# Sheet_1.net
KiCad netlist of a schematic drawn in Altium Designer
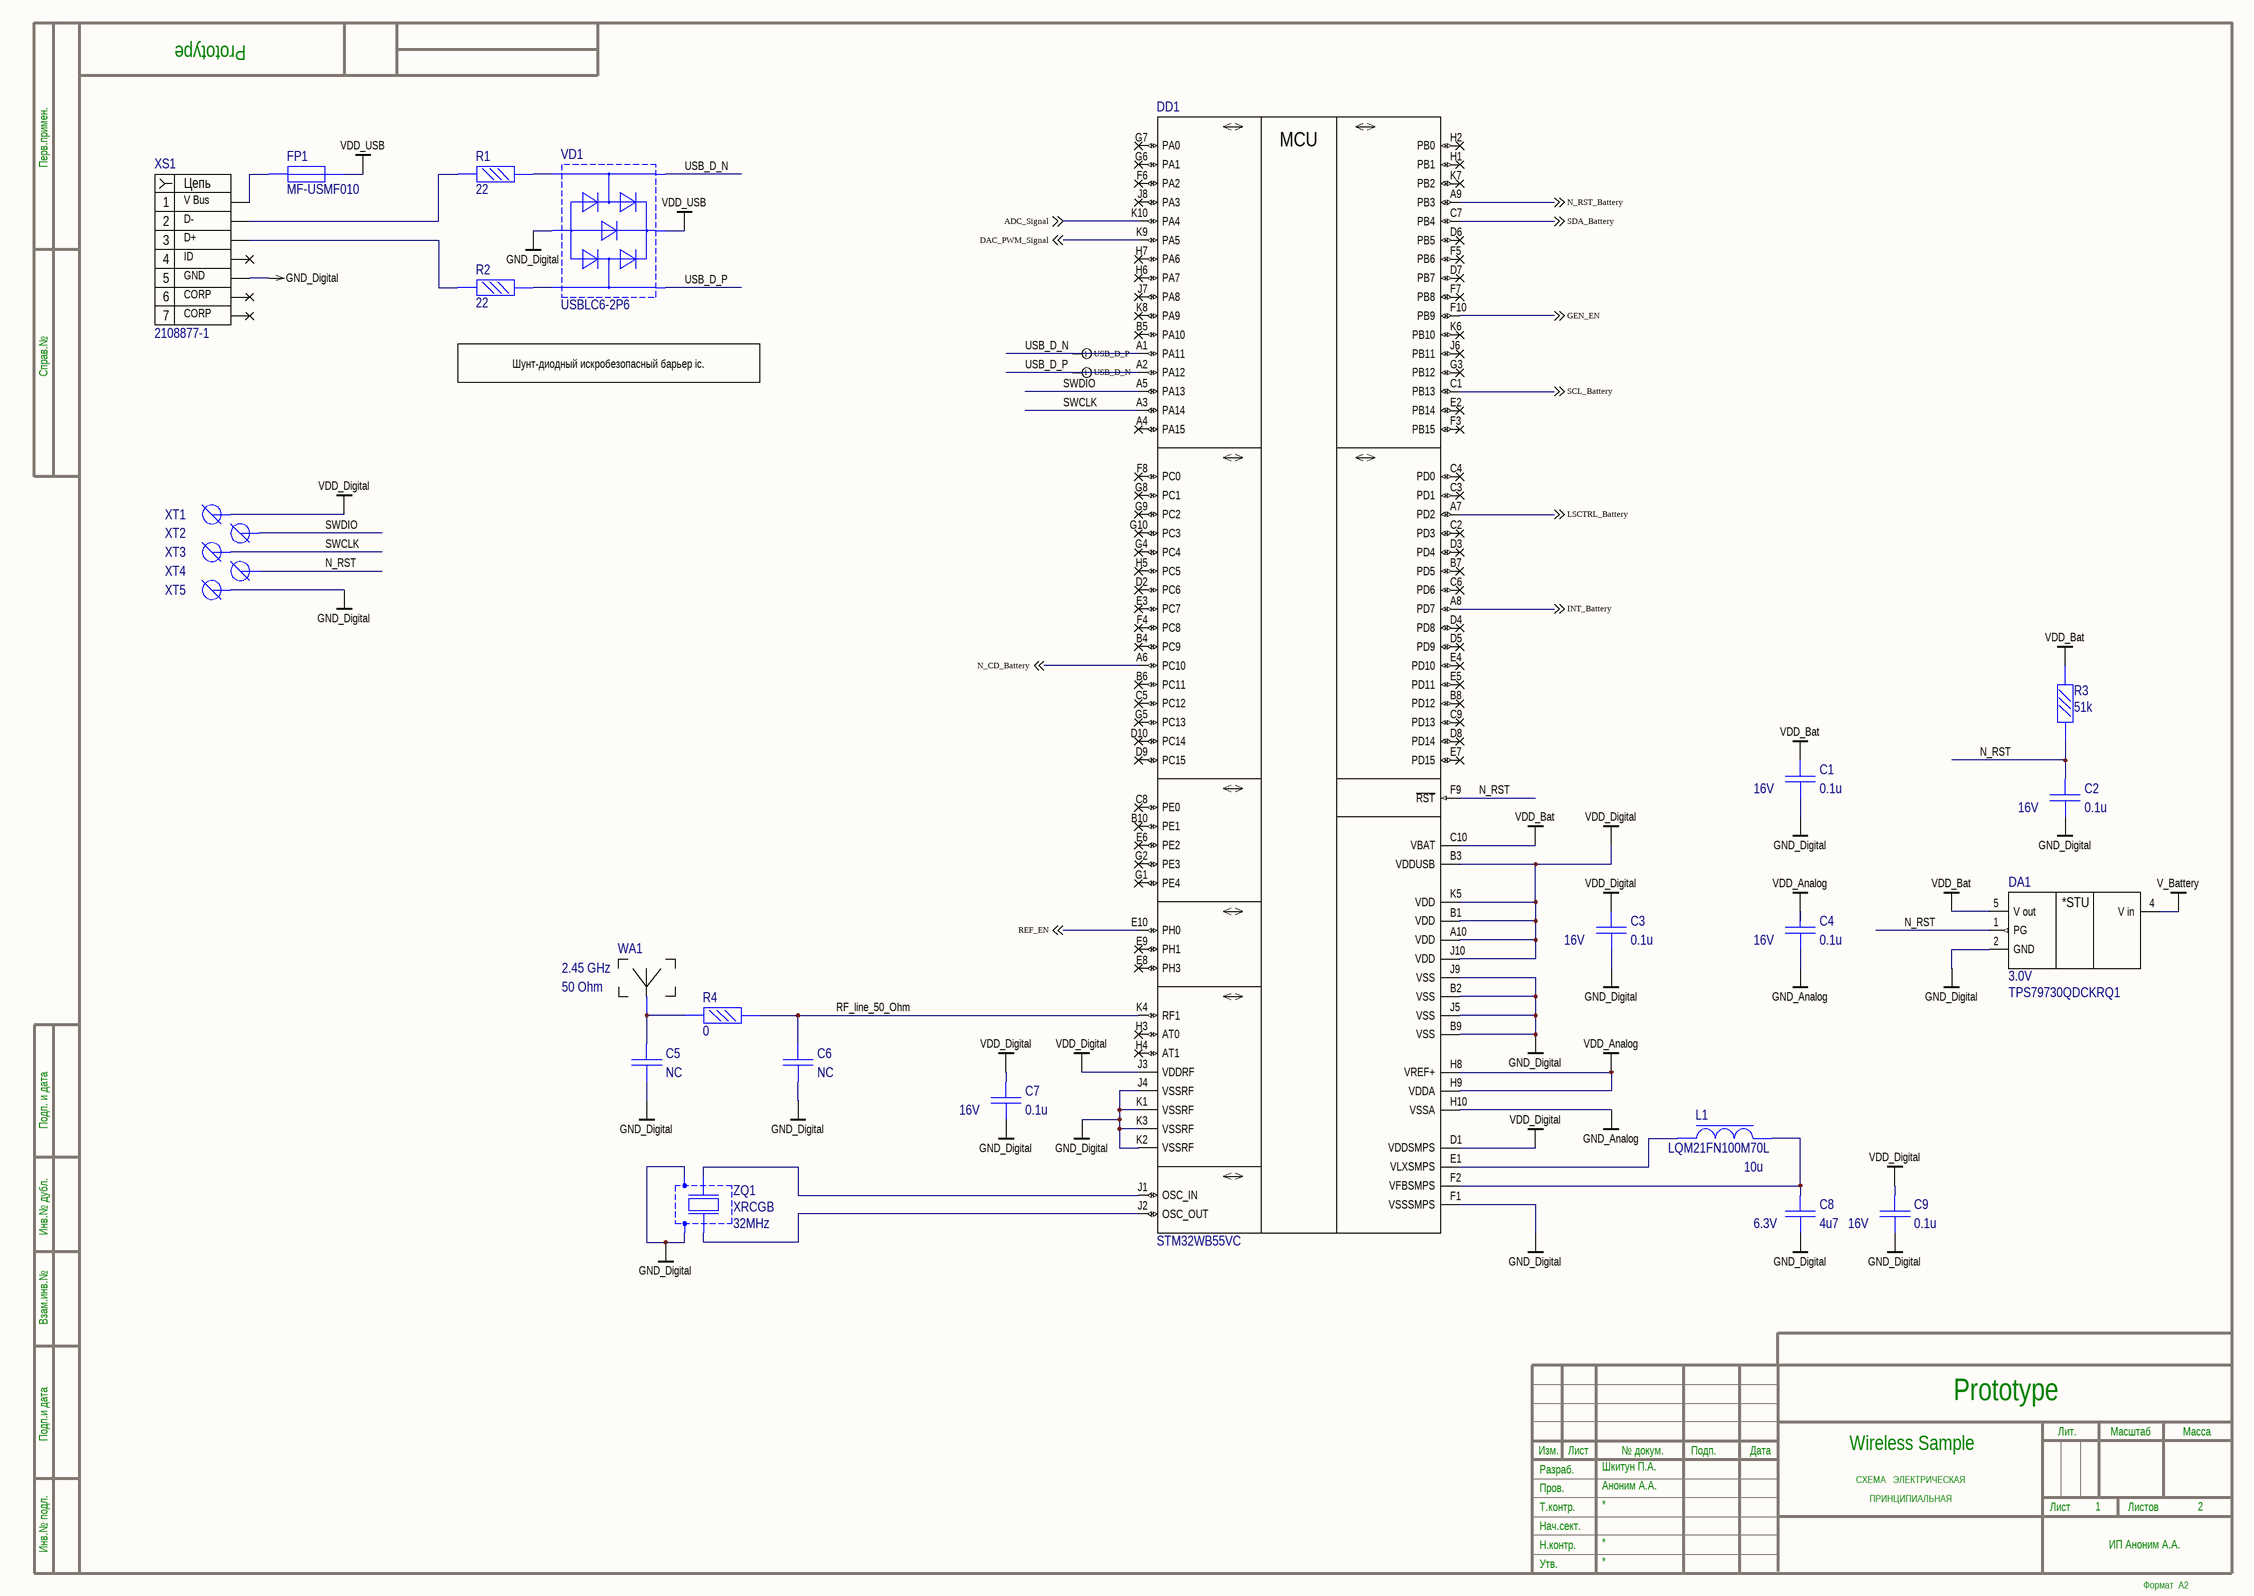
[diagram p0: Sheet_1.SchDoc]

(export (version "E")
  (design (tool "Eeschema 10.0.6"))
  (components
    (comp (ref "C1")
      (value "0.1u")
      (footprint "C0201_2")
      (fields
        (field (name "VOLTAGE") "16V")
        (field (name "Comment") "X7R")
        (field (name "PUBLISHER") "Andrew Danich")
      )
      (libsource (lib "Capacitor GOST") (part "X7R C0201"))
    )
    (comp (ref "C2")
      (value "0.1u")
      (footprint "C0201_2")
      (fields
        (field (name "VOLTAGE") "16V")
        (field (name "Comment") "X7R")
        (field (name "PUBLISHER") "Andrew Danich")
      )
      (libsource (lib "Capacitor GOST") (part "X7R C0201"))
    )
    (comp (ref "C3")
      (value "0.1u")
      (footprint "C0201_2")
      (fields
        (field (name "VOLTAGE") "16V")
        (field (name "Comment") "X7R")
        (field (name "PUBLISHER") "Andrew Danich")
      )
      (libsource (lib "Capacitor GOST") (part "X7R C0201"))
    )
    (comp (ref "C4")
      (value "0.1u")
      (footprint "C0201_2")
      (fields
        (field (name "VOLTAGE") "16V")
        (field (name "Comment") "X7R")
        (field (name "PUBLISHER") "Andrew Danich")
      )
      (libsource (lib "Capacitor GOST") (part "X7R C0201"))
    )
    (comp (ref "C5")
      (value "NC")
      (footprint "SMD Capacitor:C0201_C0G")
      (fields (field (name "Comment") "C0G") (field (name "PUBLISHER") "Andrew Danich"))
      (libsource (lib "Capacitor GOST") (part "C0G C0201"))
    )
    (comp (ref "C6")
      (value "NC")
      (footprint "SMD Capacitor:C0201_C0G")
      (fields (field (name "Comment") "C0G") (field (name "PUBLISHER") "Andrew Danich"))
      (libsource (lib "Capacitor GOST") (part "C0G C0201"))
    )
    (comp (ref "C7")
      (value "0.1u")
      (footprint "C0201_2")
      (fields
        (field (name "VOLTAGE") "16V")
        (field (name "Comment") "X7R")
        (field (name "PUBLISHER") "Andrew Danich")
      )
      (libsource (lib "Capacitor GOST") (part "X7R C0201"))
    )
    (comp (ref "C8")
      (value "4u7")
      (footprint "SMD Capacitor:C0603")
      (fields
        (field (name "VOLTAGE") "6.3V")
        (field (name "Comment") "X7R")
        (field (name "PUBLISHER") "Andrew Danich")
      )
      (libsource (lib "Capacitor GOST") (part "X7R C0603"))
    )
    (comp (ref "C9")
      (value "0.1u")
      (footprint "C0201_2")
      (fields
        (field (name "VOLTAGE") "16V")
        (field (name "Comment") "X7R")
        (field (name "PUBLISHER") "Andrew Danich")
      )
      (libsource (lib "Capacitor GOST") (part "X7R C0201"))
    )
    (comp (ref "DA1")
      (value "3.0V")
      (footprint "SMD SOT:SC70-5")
      (fields
        (field (name "NAME") "TPS79730QDCKRQ1")
        (field (name "Comment") "TPS79730QDCKRQ1")
        (field (name "PUBLISHER") "Andrew Danich")
      )
      (libsource (lib "Linear Regulator GOST") (part "TPS79730QDCKRQ1"))
    )
    (comp (ref "DD1")
      (value "STM32WB55VC")
      (footprint "SMD WLCSP:WLCSP-100")
      (fields (field (name "PUBLISHER") "Andrew Danich"))
      (libsource (lib "MCU GOST") (part "STM32WB55VC"))
    )
    (comp (ref "FP1")
      (value "MF-USMF010")
      (footprint "SMD Fuse:F1210")
      (fields (field (name "Comment") "MF-USM005") (field (name "PUBLISHER") "Andrew Danich"))
      (libsource (lib "Fuse GOST") (part "MF-USM005"))
    )
    (comp (ref "L1")
      (value "10u")
      (footprint "SMD Coil:L0805")
      (fields
        (field (name "NAME") "LQM21FN100M70L")
        (field (name "Comment") "LQM21FN100M70L")
        (field (name "PUBLISHER") "Andrew Danich")
      )
      (libsource (lib "Coil GOST") (part "LQM21FN100M70L"))
    )
    (comp (ref "R1")
      (value "22")
      (footprint "R0201_2")
      (fields (field (name "Comment") "ERJ1GN") (field (name "PUBLISHER") "Andrew Danich"))
      (libsource (lib "Resistor GOST") (part "R0201"))
    )
    (comp (ref "R2")
      (value "22")
      (footprint "R0201_2")
      (fields (field (name "Comment") "ERJ1GN") (field (name "PUBLISHER") "Andrew Danich"))
      (libsource (lib "Resistor GOST") (part "R0201"))
    )
    (comp (ref "R3")
      (value "51k")
      (footprint "R0201_2")
      (fields (field (name "Comment") "ERJ1GN") (field (name "PUBLISHER") "Andrew Danich"))
      (libsource (lib "Resistor GOST") (part "R0201"))
    )
    (comp (ref "R4")
      (value "0")
      (footprint "R0201_2")
      (fields (field (name "Comment") "ERJ1GN") (field (name "PUBLISHER") "Andrew Danich"))
      (libsource (lib "Resistor GOST") (part "R0201"))
    )
    (comp (ref "VD1")
      (value "USBLC6-2P6")
      (footprint "SMD SOT:SOT-666")
      (fields (field (name "PUBLISHER") "Andrew Danich"))
      (libsource (lib "Diode GOST") (part "USBLC6-2P6"))
    )
    (comp (ref "WA1")
      (value "2.45 GHz")
      (footprint "SMD Ant:AMCA31-2R450G-S1F-T3")
      (fields
        (field (name "Z") "50 Ohm")
        (field (name "Comment") "X7R")
        (field (name "PUBLISHER") "Andrew Danich")
      )
      (libsource (lib "Ant GOST") (part "AMCA31-2R450G-S1F-T3"))
    )
    (comp (ref "XS1")
      (value "2108877-1")
      (footprint "SMD Connector:2108877-1")
      (fields
        (field (name "7_LINE") "CORP")
        (field (name "6_LINE") "CORP")
        (field (name "1_LINE") "V Bus")
        (field (name "2_LINE") "D-")
        (field (name "3_LINE") "D+")
        (field (name "4_LINE") "ID")
        (field (name "5_LINE") "GND")
        (field (name "Comment") "2108877-1 TE Connectivity")
        (field (name "PUBLISHER") "Andrew Danich")
      )
      (libsource (lib "Connector GOST") (part "2108877-1"))
    )
    (comp (ref "XT1")
      (value "Test_Pin")
      (footprint "SMD Connector:TEST_PIN_2")
      (fields (field (name "PUBLISHER") "Andrew Danich"))
      (libsource (lib "Connector GOST") (part "Test_Pin"))
    )
    (comp (ref "XT2")
      (value "Test_Pin")
      (footprint "SMD Connector:TEST_PIN_2")
      (fields (field (name "PUBLISHER") "Andrew Danich"))
      (libsource (lib "Connector GOST") (part "Test_Pin"))
    )
    (comp (ref "XT3")
      (value "Test_Pin")
      (footprint "SMD Connector:TEST_PIN_2")
      (fields (field (name "PUBLISHER") "Andrew Danich"))
      (libsource (lib "Connector GOST") (part "Test_Pin"))
    )
    (comp (ref "XT4")
      (value "Test_Pin")
      (footprint "SMD Connector:TEST_PIN_2")
      (fields (field (name "PUBLISHER") "Andrew Danich"))
      (libsource (lib "Connector GOST") (part "Test_Pin"))
    )
    (comp (ref "XT5")
      (value "Test_Pin")
      (footprint "SMD Connector:TEST_PIN_2")
      (fields (field (name "PUBLISHER") "Andrew Danich"))
      (libsource (lib "Connector GOST") (part "Test_Pin"))
    )
    (comp (ref "ZQ1")
      (value "32MHz")
      (footprint "SMD Crystal:XRCGB")
      (fields
        (field (name "MODEL") "XRCGB")
        (field (name "Comment") "XRCGB")
        (field (name "PUBLISHER") "Andrew Danich")
      )
      (libsource (lib "Crystal GOST") (part "XRCGB"))
    )
  )
  (nets
    (net (code "1") (name "/N_RST") (class "Default")
      (node (ref "C2") (pin "1") (pinfunction "1_1") (pintype "passive"))
      (node (ref "DA1") (pin "1") (pinfunction "PG_1") (pintype "output"))
      (node (ref "DD1") (pin "F9") (pinfunction "~{RST}_F9") (pintype "input"))
      (node (ref "R3") (pin "1") (pinfunction "1_1") (pintype "passive"))
      (node (ref "XT4") (pin "1") (pintype "passive"))
    )
    (net (code "2") (name "/RF_line_50_Ohm") (class "Default")
      (node (ref "C6") (pin "1") (pinfunction "1_1") (pintype "passive"))
      (node (ref "DD1") (pin "K4") (pinfunction "RF1_K4") (pintype "bidirectional"))
      (node (ref "R4") (pin "2") (pinfunction "2_2") (pintype "passive"))
    )
    (net (code "3") (name "/SWCLK") (class "Default")
      (node (ref "DD1") (pin "A3") (pinfunction "PA14_A3") (pintype "bidirectional"))
      (node (ref "XT3") (pin "1") (pintype "passive"))
    )
    (net (code "4") (name "/SWDIO") (class "Default")
      (node (ref "DD1") (pin "A5") (pinfunction "PA13_A5") (pintype "bidirectional"))
      (node (ref "XT2") (pin "1") (pintype "passive"))
    )
    (net (code "5") (name "/USB_D_N") (class "Default")
      (node (ref "DD1") (pin "A1") (pinfunction "PA11_A1") (pintype "bidirectional"))
      (node (ref "VD1") (pin "4") (pinfunction "IO_21_4") (pintype "passive"))
    )
    (net (code "6") (name "/USB_D_P") (class "Default")
      (node (ref "DD1") (pin "A2") (pinfunction "PA12_A2") (pintype "bidirectional"))
      (node (ref "VD1") (pin "6") (pinfunction "IO_11_6") (pintype "passive"))
    )
    (net (code "7") (name "ADC_Signal") (class "Default")
      (node (ref "DD1") (pin "K10") (pinfunction "PA4_K10") (pintype "bidirectional"))
    )
    (net (code "8") (name "DAC_PWM_Signal") (class "Default")
      (node (ref "DD1") (pin "K9") (pinfunction "PA5_K9") (pintype "bidirectional"))
    )
    (net (code "9") (name "GEN_EN") (class "Default")
      (node (ref "DD1") (pin "F10") (pinfunction "PB9_F10") (pintype "bidirectional"))
    )
    (net (code "10") (name "GND_Analog") (class "Default")
      (node (ref "C4") (pin "2") (pinfunction "2_2") (pintype "passive"))
      (node (ref "DD1") (pin "H10") (pinfunction "VSSA_H10") (pintype "power_in"))
    )
    (net (code "11") (name "GND_Digital") (class "Default")
      (node (ref "C1") (pin "2") (pinfunction "2_2") (pintype "passive"))
      (node (ref "C2") (pin "2") (pinfunction "2_2") (pintype "passive"))
      (node (ref "C3") (pin "2") (pinfunction "2_2") (pintype "passive"))
      (node (ref "C5") (pin "2") (pinfunction "2_2") (pintype "passive"))
      (node (ref "C6") (pin "2") (pinfunction "2_2") (pintype "passive"))
      (node (ref "C7") (pin "2") (pinfunction "2_2") (pintype "passive"))
      (node (ref "C8") (pin "2") (pinfunction "2_2") (pintype "passive"))
      (node (ref "C9") (pin "2") (pinfunction "2_2") (pintype "passive"))
      (node (ref "DA1") (pin "2") (pinfunction "GND_2") (pintype "power_in"))
      (node (ref "DD1") (pin "B2") (pinfunction "VSS_B2") (pintype "power_in"))
      (node (ref "DD1") (pin "B9") (pinfunction "VSS_B9") (pintype "power_in"))
      (node (ref "DD1") (pin "F1") (pinfunction "VSSSMPS_F1") (pintype "power_in"))
      (node (ref "DD1") (pin "J4") (pinfunction "VSSRF_J4") (pintype "power_in"))
      (node (ref "DD1") (pin "J5") (pinfunction "VSS_J5") (pintype "power_in"))
      (node (ref "DD1") (pin "J9") (pinfunction "VSS_J9") (pintype "power_in"))
      (node (ref "DD1") (pin "K1") (pinfunction "VSSRF_K1") (pintype "power_in"))
      (node (ref "DD1") (pin "K2") (pinfunction "VSSRF_K2") (pintype "power_in"))
      (node (ref "DD1") (pin "K3") (pinfunction "VSSRF_K3") (pintype "power_in"))
      (node (ref "VD1") (pin "2") (pinfunction "GND_2") (pintype "passive"))
      (node (ref "XS1") (pin "5") (pinfunction "GND_5") (pintype "passive"))
      (node (ref "XT5") (pin "1") (pintype "passive"))
      (node (ref "ZQ1") (pin "2") (pinfunction "2_2") (pintype "passive"))
      (node (ref "ZQ1") (pin "4") (pinfunction "4_4") (pintype "passive"))
    )
    (net (code "12") (name "INT_Battery") (class "Default")
      (node (ref "DD1") (pin "A8") (pinfunction "PD7_A8") (pintype "bidirectional"))
    )
    (net (code "13") (name "LSCTRL_Battery") (class "Default")
      (node (ref "DD1") (pin "A7") (pinfunction "PD2_A7") (pintype "bidirectional"))
    )
    (net (code "14") (name "N_CD_Battery") (class "Default")
      (node (ref "DD1") (pin "A6") (pinfunction "PC10_A6") (pintype "bidirectional"))
    )
    (net (code "15") (name "N_RST_Battery") (class "Default")
      (node (ref "DD1") (pin "A9") (pinfunction "PB3_A9") (pintype "bidirectional"))
    )
    (net (code "16") (name "Net-(C5-Pad1)") (class "Default")
      (node (ref "C5") (pin "1") (pinfunction "1_1") (pintype "passive"))
      (node (ref "R4") (pin "1") (pinfunction "1_1") (pintype "passive"))
      (node (ref "WA1") (pin "1") (pinfunction "1_1") (pintype "passive"))
    )
    (net (code "17") (name "Net-(DD1-OSC_IN)") (class "Default")
      (node (ref "DD1") (pin "J1") (pinfunction "OSC_IN_J1") (pintype "bidirectional"))
      (node (ref "ZQ1") (pin "3") (pinfunction "3_3") (pintype "passive"))
    )
    (net (code "18") (name "Net-(DD1-OSC_OUT)") (class "Default")
      (node (ref "DD1") (pin "J2") (pinfunction "OSC_OUT_J2") (pintype "bidirectional"))
      (node (ref "ZQ1") (pin "1") (pinfunction "1_1") (pintype "passive"))
    )
    (net (code "19") (name "Net-(DD1-VFBSMPS)") (class "Default")
      (node (ref "C8") (pin "1") (pinfunction "1_1") (pintype "passive"))
      (node (ref "DD1") (pin "F2") (pinfunction "VFBSMPS_F2") (pintype "power_in"))
      (node (ref "L1") (pin "2") (pinfunction "2_2") (pintype "passive"))
    )
    (net (code "20") (name "Net-(DD1-VLXSMPS)") (class "Default")
      (node (ref "DD1") (pin "E1") (pinfunction "VLXSMPS_E1") (pintype "power_in"))
      (node (ref "L1") (pin "1") (pinfunction "1_1") (pintype "passive"))
    )
    (net (code "21") (name "Net-(VD1-IO_10)") (class "Default")
      (node (ref "R2") (pin "2") (pinfunction "2_2") (pintype "passive"))
      (node (ref "VD1") (pin "1") (pinfunction "IO_10_1") (pintype "passive"))
    )
    (net (code "22") (name "Net-(VD1-IO_20)") (class "Default")
      (node (ref "R1") (pin "2") (pinfunction "2_2") (pintype "passive"))
      (node (ref "VD1") (pin "3") (pinfunction "IO_20_3") (pintype "passive"))
    )
    (net (code "23") (name "Net-(XS1-D+)") (class "Default")
      (node (ref "R2") (pin "1") (pinfunction "1_1") (pintype "passive"))
      (node (ref "XS1") (pin "3") (pinfunction "D+_3") (pintype "passive"))
    )
    (net (code "24") (name "Net-(XS1-D-)") (class "Default")
      (node (ref "R1") (pin "1") (pinfunction "1_1") (pintype "passive"))
      (node (ref "XS1") (pin "2") (pinfunction "D-_2") (pintype "passive"))
    )
    (net (code "25") (name "Net-(XS1-V_bus)") (class "Default")
      (node (ref "FP1") (pin "1") (pinfunction "1_1") (pintype "passive"))
      (node (ref "XS1") (pin "1") (pinfunction "V_bus_1") (pintype "passive"))
    )
    (net (code "26") (name "REF_EN") (class "Default")
      (node (ref "DD1") (pin "E10") (pinfunction "PH0_E10") (pintype "bidirectional"))
    )
    (net (code "27") (name "SCL_Battery") (class "Default")
      (node (ref "DD1") (pin "C1") (pinfunction "PB13_C1") (pintype "bidirectional"))
    )
    (net (code "28") (name "SDA_Battery") (class "Default")
      (node (ref "DD1") (pin "C7") (pinfunction "PB4_C7") (pintype "bidirectional"))
    )
    (net (code "29") (name "VDD_Analog") (class "Default")
      (node (ref "C4") (pin "1") (pinfunction "1_1") (pintype "passive"))
      (node (ref "DD1") (pin "H8") (pinfunction "VREF+_H8") (pintype "power_in"))
      (node (ref "DD1") (pin "H9") (pinfunction "VDDA_H9") (pintype "power_in"))
    )
    (net (code "30") (name "VDD_Bat") (class "Default")
      (node (ref "C1") (pin "1") (pinfunction "1_1") (pintype "passive"))
      (node (ref "DA1") (pin "5") (pinfunction "V_out_5") (pintype "power_in"))
      (node (ref "DD1") (pin "C10") (pinfunction "VBAT_C10") (pintype "power_in"))
      (node (ref "R3") (pin "2") (pinfunction "2_2") (pintype "passive"))
    )
    (net (code "31") (name "VDD_Digital") (class "Default")
      (node (ref "C3") (pin "1") (pinfunction "1_1") (pintype "passive"))
      (node (ref "C7") (pin "1") (pinfunction "1_1") (pintype "passive"))
      (node (ref "C9") (pin "1") (pinfunction "1_1") (pintype "passive"))
      (node (ref "DD1") (pin "A10") (pinfunction "VDD_A10") (pintype "power_in"))
      (node (ref "DD1") (pin "B1") (pinfunction "VDD_B1") (pintype "power_in"))
      (node (ref "DD1") (pin "B3") (pinfunction "VDDUSB_B3") (pintype "power_in"))
      (node (ref "DD1") (pin "D1") (pinfunction "VDDSMPS_D1") (pintype "power_in"))
      (node (ref "DD1") (pin "J10") (pinfunction "VDD_J10") (pintype "power_in"))
      (node (ref "DD1") (pin "J3") (pinfunction "VDDRF_J3") (pintype "power_in"))
      (node (ref "DD1") (pin "K5") (pinfunction "VDD_K5") (pintype "power_in"))
      (node (ref "XT1") (pin "1") (pintype "passive"))
    )
    (net (code "32") (name "VDD_USB") (class "Default")
      (node (ref "FP1") (pin "2") (pinfunction "2_2") (pintype "passive"))
      (node (ref "VD1") (pin "5") (pinfunction "V_bus_5") (pintype "passive"))
    )
    (net (code "33") (name "V_Battery") (class "Default")
      (node (ref "DA1") (pin "4") (pinfunction "V_in_4") (pintype "power_in"))
    )
    (net (code "34") (name "unconnected-(DD1-AT0-PadH3)") (class "Default")
      (node (ref "DD1") (pin "H3") (pinfunction "AT0_H3") (pintype "bidirectional+no_connect"))
    )
    (net (code "35") (name "unconnected-(DD1-AT1-PadH4)") (class "Default")
      (node (ref "DD1") (pin "H4") (pinfunction "AT1_H4") (pintype "bidirectional+no_connect"))
    )
    (net (code "36") (name "unconnected-(DD1-PA0-PadG7)") (class "Default")
      (node (ref "DD1") (pin "G7") (pinfunction "PA0_G7") (pintype "bidirectional+no_connect"))
    )
    (net (code "37") (name "unconnected-(DD1-PA1-PadG6)") (class "Default")
      (node (ref "DD1") (pin "G6") (pinfunction "PA1_G6") (pintype "bidirectional+no_connect"))
    )
    (net (code "38") (name "unconnected-(DD1-PA2-PadF6)") (class "Default")
      (node (ref "DD1") (pin "F6") (pinfunction "PA2_F6") (pintype "bidirectional+no_connect"))
    )
    (net (code "39") (name "unconnected-(DD1-PA3-PadJ8)") (class "Default")
      (node (ref "DD1") (pin "J8") (pinfunction "PA3_J8") (pintype "bidirectional+no_connect"))
    )
    (net (code "40") (name "unconnected-(DD1-PA6-PadH7)") (class "Default")
      (node (ref "DD1") (pin "H7") (pinfunction "PA6_H7") (pintype "bidirectional+no_connect"))
    )
    (net (code "41") (name "unconnected-(DD1-PA7-PadH6)") (class "Default")
      (node (ref "DD1") (pin "H6") (pinfunction "PA7_H6") (pintype "bidirectional+no_connect"))
    )
    (net (code "42") (name "unconnected-(DD1-PA8-PadJ7)") (class "Default")
      (node (ref "DD1") (pin "J7") (pinfunction "PA8_J7") (pintype "bidirectional+no_connect"))
    )
    (net (code "43") (name "unconnected-(DD1-PA9-PadK8)") (class "Default")
      (node (ref "DD1") (pin "K8") (pinfunction "PA9_K8") (pintype "bidirectional+no_connect"))
    )
    (net (code "44") (name "unconnected-(DD1-PA10-PadB5)") (class "Default")
      (node (ref "DD1") (pin "B5") (pinfunction "PA10_B5") (pintype "bidirectional+no_connect"))
    )
    (net (code "45") (name "unconnected-(DD1-PA15-PadA4)") (class "Default")
      (node (ref "DD1") (pin "A4") (pinfunction "PA15_A4") (pintype "bidirectional+no_connect"))
    )
    (net (code "46") (name "unconnected-(DD1-PB0-PadH2)") (class "Default")
      (node (ref "DD1") (pin "H2") (pinfunction "PB0_H2") (pintype "bidirectional+no_connect"))
    )
    (net (code "47") (name "unconnected-(DD1-PB1-PadH1)") (class "Default")
      (node (ref "DD1") (pin "H1") (pinfunction "PB1_H1") (pintype "bidirectional+no_connect"))
    )
    (net (code "48") (name "unconnected-(DD1-PB2-PadK7)") (class "Default")
      (node (ref "DD1") (pin "K7") (pinfunction "PB2_K7") (pintype "bidirectional+no_connect"))
    )
    (net (code "49") (name "unconnected-(DD1-PB5-PadD6)") (class "Default")
      (node (ref "DD1") (pin "D6") (pinfunction "PB5_D6") (pintype "bidirectional+no_connect"))
    )
    (net (code "50") (name "unconnected-(DD1-PB6-PadF5)") (class "Default")
      (node (ref "DD1") (pin "F5") (pinfunction "PB6_F5") (pintype "bidirectional+no_connect"))
    )
    (net (code "51") (name "unconnected-(DD1-PB7-PadD7)") (class "Default")
      (node (ref "DD1") (pin "D7") (pinfunction "PB7_D7") (pintype "bidirectional+no_connect"))
    )
    (net (code "52") (name "unconnected-(DD1-PB8-PadF7)") (class "Default")
      (node (ref "DD1") (pin "F7") (pinfunction "PB8_F7") (pintype "bidirectional+no_connect"))
    )
    (net (code "53") (name "unconnected-(DD1-PB10-PadK6)") (class "Default")
      (node (ref "DD1") (pin "K6") (pinfunction "PB10_K6") (pintype "bidirectional+no_connect"))
    )
    (net (code "54") (name "unconnected-(DD1-PB11-PadJ6)") (class "Default")
      (node (ref "DD1") (pin "J6") (pinfunction "PB11_J6") (pintype "bidirectional+no_connect"))
    )
    (net (code "55") (name "unconnected-(DD1-PB12-PadG3)") (class "Default")
      (node (ref "DD1") (pin "G3") (pinfunction "PB12_G3") (pintype "bidirectional+no_connect"))
    )
    (net (code "56") (name "unconnected-(DD1-PB14-PadE2)") (class "Default")
      (node (ref "DD1") (pin "E2") (pinfunction "PB14_E2") (pintype "bidirectional+no_connect"))
    )
    (net (code "57") (name "unconnected-(DD1-PB15-PadF3)") (class "Default")
      (node (ref "DD1") (pin "F3") (pinfunction "PB15_F3") (pintype "bidirectional+no_connect"))
    )
    (net (code "58") (name "unconnected-(DD1-PC0-PadF8)") (class "Default")
      (node (ref "DD1") (pin "F8") (pinfunction "PC0_F8") (pintype "bidirectional+no_connect"))
    )
    (net (code "59") (name "unconnected-(DD1-PC1-PadG8)") (class "Default")
      (node (ref "DD1") (pin "G8") (pinfunction "PC1_G8") (pintype "bidirectional+no_connect"))
    )
    (net (code "60") (name "unconnected-(DD1-PC2-PadG9)") (class "Default")
      (node (ref "DD1") (pin "G9") (pinfunction "PC2_G9") (pintype "bidirectional+no_connect"))
    )
    (net (code "61") (name "unconnected-(DD1-PC3-PadG10)") (class "Default")
      (node (ref "DD1") (pin "G10") (pinfunction "PC3_G10") (pintype "bidirectional+no_connect"))
    )
    (net (code "62") (name "unconnected-(DD1-PC4-PadG4)") (class "Default")
      (node (ref "DD1") (pin "G4") (pinfunction "PC4_G4") (pintype "bidirectional+no_connect"))
    )
    (net (code "63") (name "unconnected-(DD1-PC5-PadH5)") (class "Default")
      (node (ref "DD1") (pin "H5") (pinfunction "PC5_H5") (pintype "bidirectional+no_connect"))
    )
    (net (code "64") (name "unconnected-(DD1-PC6-PadD2)") (class "Default")
      (node (ref "DD1") (pin "D2") (pinfunction "PC6_D2") (pintype "bidirectional+no_connect"))
    )
    (net (code "65") (name "unconnected-(DD1-PC7-PadE3)") (class "Default")
      (node (ref "DD1") (pin "E3") (pinfunction "PC7_E3") (pintype "bidirectional+no_connect"))
    )
    (net (code "66") (name "unconnected-(DD1-PC8-PadF4)") (class "Default")
      (node (ref "DD1") (pin "F4") (pinfunction "PC8_F4") (pintype "bidirectional+no_connect"))
    )
    (net (code "67") (name "unconnected-(DD1-PC9-PadB4)") (class "Default")
      (node (ref "DD1") (pin "B4") (pinfunction "PC9_B4") (pintype "bidirectional+no_connect"))
    )
    (net (code "68") (name "unconnected-(DD1-PC11-PadB6)") (class "Default")
      (node (ref "DD1") (pin "B6") (pinfunction "PC11_B6") (pintype "bidirectional+no_connect"))
    )
    (net (code "69") (name "unconnected-(DD1-PC12-PadC5)") (class "Default")
      (node (ref "DD1") (pin "C5") (pinfunction "PC12_C5") (pintype "bidirectional+no_connect"))
    )
    (net (code "70") (name "unconnected-(DD1-PC13-PadG5)") (class "Default")
      (node (ref "DD1") (pin "G5") (pinfunction "PC13_G5") (pintype "bidirectional+no_connect"))
    )
    (net (code "71") (name "unconnected-(DD1-PC14-PadD10)") (class "Default")
      (node (ref "DD1") (pin "D10") (pinfunction "PC14_D10") (pintype "bidirectional+no_connect"))
    )
    (net (code "72") (name "unconnected-(DD1-PC15-PadD9)") (class "Default")
      (node (ref "DD1") (pin "D9") (pinfunction "PC15_D9") (pintype "bidirectional+no_connect"))
    )
    (net (code "73") (name "unconnected-(DD1-PD0-PadC4)") (class "Default")
      (node (ref "DD1") (pin "C4") (pinfunction "PD0_C4") (pintype "bidirectional+no_connect"))
    )
    (net (code "74") (name "unconnected-(DD1-PD1-PadC3)") (class "Default")
      (node (ref "DD1") (pin "C3") (pinfunction "PD1_C3") (pintype "bidirectional+no_connect"))
    )
    (net (code "75") (name "unconnected-(DD1-PD3-PadC2)") (class "Default")
      (node (ref "DD1") (pin "C2") (pinfunction "PD3_C2") (pintype "bidirectional+no_connect"))
    )
    (net (code "76") (name "unconnected-(DD1-PD4-PadD3)") (class "Default")
      (node (ref "DD1") (pin "D3") (pinfunction "PD4_D3") (pintype "bidirectional+no_connect"))
    )
    (net (code "77") (name "unconnected-(DD1-PD5-PadB7)") (class "Default")
      (node (ref "DD1") (pin "B7") (pinfunction "PD5_B7") (pintype "bidirectional+no_connect"))
    )
    (net (code "78") (name "unconnected-(DD1-PD6-PadC6)") (class "Default")
      (node (ref "DD1") (pin "C6") (pinfunction "PD6_C6") (pintype "bidirectional+no_connect"))
    )
    (net (code "79") (name "unconnected-(DD1-PD8-PadD4)") (class "Default")
      (node (ref "DD1") (pin "D4") (pinfunction "PD8_D4") (pintype "bidirectional+no_connect"))
    )
    (net (code "80") (name "unconnected-(DD1-PD9-PadD5)") (class "Default")
      (node (ref "DD1") (pin "D5") (pinfunction "PD9_D5") (pintype "bidirectional+no_connect"))
    )
    (net (code "81") (name "unconnected-(DD1-PD10-PadE4)") (class "Default")
      (node (ref "DD1") (pin "E4") (pinfunction "PD10_E4") (pintype "bidirectional+no_connect"))
    )
    (net (code "82") (name "unconnected-(DD1-PD11-PadE5)") (class "Default")
      (node (ref "DD1") (pin "E5") (pinfunction "PD11_E5") (pintype "bidirectional+no_connect"))
    )
    (net (code "83") (name "unconnected-(DD1-PD12-PadB8)") (class "Default")
      (node (ref "DD1") (pin "B8") (pinfunction "PD12_B8") (pintype "bidirectional+no_connect"))
    )
    (net (code "84") (name "unconnected-(DD1-PD13-PadC9)") (class "Default")
      (node (ref "DD1") (pin "C9") (pinfunction "PD13_C9") (pintype "bidirectional+no_connect"))
    )
    (net (code "85") (name "unconnected-(DD1-PD14-PadD8)") (class "Default")
      (node (ref "DD1") (pin "D8") (pinfunction "PD14_D8") (pintype "bidirectional+no_connect"))
    )
    (net (code "86") (name "unconnected-(DD1-PD15-PadE7)") (class "Default")
      (node (ref "DD1") (pin "E7") (pinfunction "PD15_E7") (pintype "bidirectional+no_connect"))
    )
    (net (code "87") (name "unconnected-(DD1-PE0-PadC8)") (class "Default")
      (node (ref "DD1") (pin "C8") (pinfunction "PE0_C8") (pintype "bidirectional+no_connect"))
    )
    (net (code "88") (name "unconnected-(DD1-PE1-PadB10)") (class "Default")
      (node (ref "DD1") (pin "B10") (pinfunction "PE1_B10") (pintype "bidirectional+no_connect"))
    )
    (net (code "89") (name "unconnected-(DD1-PE2-PadE6)") (class "Default")
      (node (ref "DD1") (pin "E6") (pinfunction "PE2_E6") (pintype "bidirectional+no_connect"))
    )
    (net (code "90") (name "unconnected-(DD1-PE3-PadG2)") (class "Default")
      (node (ref "DD1") (pin "G2") (pinfunction "PE3_G2") (pintype "bidirectional+no_connect"))
    )
    (net (code "91") (name "unconnected-(DD1-PE4-PadG1)") (class "Default")
      (node (ref "DD1") (pin "G1") (pinfunction "PE4_G1") (pintype "bidirectional+no_connect"))
    )
    (net (code "92") (name "unconnected-(DD1-PH1-PadE9)") (class "Default")
      (node (ref "DD1") (pin "E9") (pinfunction "PH1_E9") (pintype "bidirectional+no_connect"))
    )
    (net (code "93") (name "unconnected-(DD1-PH3-PadE8)") (class "Default")
      (node (ref "DD1") (pin "E8") (pinfunction "PH3_E8") (pintype "bidirectional+no_connect"))
    )
    (net (code "94") (name "unconnected-(XS1-Corp_1-Pad6)") (class "Default")
      (node (ref "XS1") (pin "6") (pinfunction "Corp_1_6") (pintype "passive+no_connect"))
    )
    (net (code "95") (name "unconnected-(XS1-Corp_2-Pad7)") (class "Default")
      (node (ref "XS1") (pin "7") (pinfunction "Corp_2_7") (pintype "passive+no_connect"))
    )
    (net (code "96") (name "unconnected-(XS1-NC-Pad4)") (class "Default")
      (node (ref "XS1") (pin "4") (pinfunction "NC_4") (pintype "passive+no_connect"))
    )
  )
)
